# Grill_simple_bord_onedirect.net
KiCad netlist of a schematic drawn in EAGLE
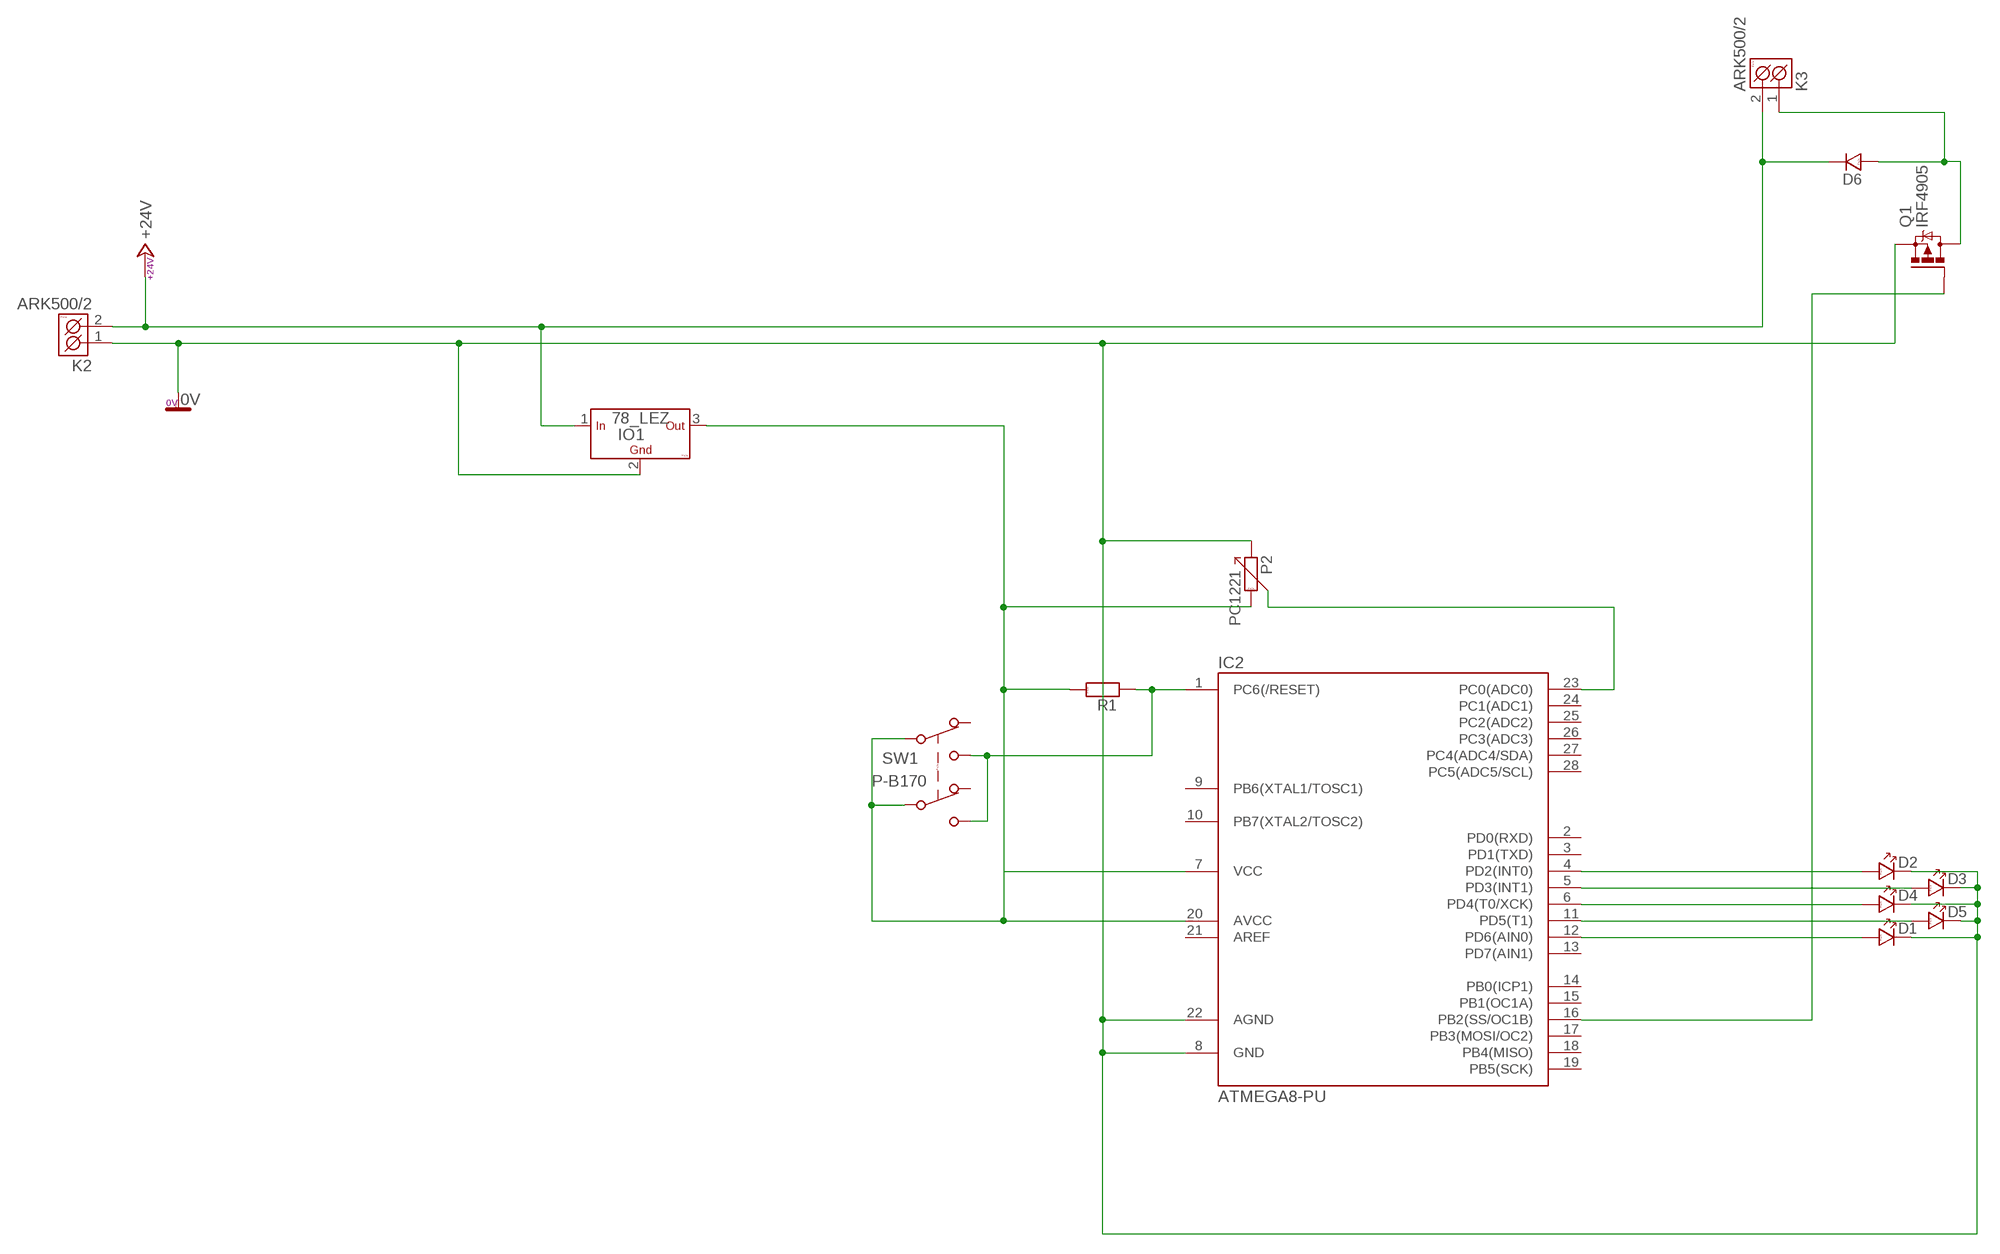
[diagram p0: schematic, sheet 1]

(export (version "E")
  (design (tool "Eeschema 10.0.6"))
  (components
    (comp (ref "D1")
      (value "LED_5")
      (footprint "eagle-import:LED_5")
      (libsource (lib "eagle-import") (part "LED_5"))
    )
    (comp (ref "D2")
      (value "LED_5")
      (footprint "eagle-import:LED_5")
      (libsource (lib "eagle-import") (part "LED_5"))
    )
    (comp (ref "D3")
      (value "LED_5")
      (footprint "eagle-import:LED_5")
      (libsource (lib "eagle-import") (part "LED_5"))
    )
    (comp (ref "D4")
      (value "LED_5")
      (footprint "eagle-import:LED_5")
      (libsource (lib "eagle-import") (part "LED_5"))
    )
    (comp (ref "D5")
      (value "LED_5")
      (footprint "eagle-import:LED_5")
      (libsource (lib "eagle-import") (part "LED_5"))
    )
    (comp (ref "D6")
      (value "D_10")
      (footprint "eagle-import:DO41")
      (libsource (lib "eagle-import") (part "D_10"))
    )
    (comp (ref "IC2")
      (value "ATMEGA8-PU")
      (footprint "eagle-import:DIL28-3")
      (libsource (lib "eagle-import") (part "ATMEGA8-PU"))
    )
    (comp (ref "IO1")
      (value "78_LEZ")
      (footprint "eagle-import:TO-220")
      (libsource (lib "eagle-import") (part "78?_LEZ"))
    )
    (comp (ref "K2")
      (value "ARK500/2")
      (footprint "eagle-import:ARK500_2")
      (libsource (lib "eagle-import") (part "ARK500/2"))
    )
    (comp (ref "K3")
      (value "ARK500/2")
      (footprint "eagle-import:ARK500_2")
      (libsource (lib "eagle-import") (part "ARK500/2"))
    )
    (comp (ref "P2")
      (value "PC1221")
      (footprint "eagle-import:PC1221")
      (libsource (lib "eagle-import") (part "PC1221"))
    )
    (comp (ref "Q1")
      (value "IRF4905")
      (footprint "eagle-import:TO220BH")
      (libsource (lib "eagle-import") (part "IRF4905"))
    )
    (comp (ref "R1")
      (value "R_7,5")
      (footprint "eagle-import:R-7,5")
      (libsource (lib "eagle-import") (part "R_7,5"))
    )
    (comp (ref "SW1")
      (value "P-B170")
      (footprint "eagle-import:P-B170")
      (libsource (lib "eagle-import") (part "P-B170"))
    )
  )
  (nets
    (net (code "1") (name "+24V") (class "Default")
      (node (ref "D6") (pin "K") (pinfunction "K_K") (pintype "passive"))
      (node (ref "IO1") (pin "1") (pinfunction "IN_1") (pintype "passive"))
      (node (ref "K2") (pin "2") (pinfunction "K2_2") (pintype "passive"))
      (node (ref "K3") (pin "2") (pinfunction "K2_2") (pintype "passive"))
    )
    (net (code "2") (name "0V") (class "Default")
      (node (ref "D1") (pin "K") (pinfunction "K_K") (pintype "passive"))
      (node (ref "D2") (pin "K") (pinfunction "K_K") (pintype "passive"))
      (node (ref "D3") (pin "K") (pinfunction "K_K") (pintype "passive"))
      (node (ref "D4") (pin "K") (pinfunction "K_K") (pintype "passive"))
      (node (ref "D5") (pin "K") (pinfunction "K_K") (pintype "passive"))
      (node (ref "IC2") (pin "22") (pinfunction "AGND_22") (pintype "power_in"))
      (node (ref "IC2") (pin "8") (pinfunction "GND_8") (pintype "power_in"))
      (node (ref "IO1") (pin "2") (pinfunction "GND_2") (pintype "passive"))
      (node (ref "K2") (pin "1") (pinfunction "K1_1") (pintype "passive"))
      (node (ref "P2") (pin "1") (pinfunction "1_1") (pintype "passive"))
      (node (ref "Q1") (pin "S") (pinfunction "S_S") (pintype "passive"))
    )
    (net (code "3") (name "Net-(IC2-AVCC)") (class "Default")
      (node (ref "IC2") (pin "20") (pinfunction "AVCC_20") (pintype "passive"))
      (node (ref "IC2") (pin "7") (pinfunction "VCC_7") (pintype "power_in"))
      (node (ref "IO1") (pin "3") (pinfunction "OUT_3") (pintype "passive"))
      (node (ref "P2") (pin "2") (pinfunction "2_2") (pintype "passive"))
      (node (ref "R1") (pin "2") (pinfunction "2_2") (pintype "passive"))
      (node (ref "SW1") (pin "3") (pinfunction "X1_3") (pintype "passive"))
      (node (ref "SW1") (pin "6") (pinfunction "X2_6") (pintype "passive"))
    )
    (net (code "4") (name "Net-(IC2-PB2(SS{slash}OC1B))") (class "Default")
      (node (ref "IC2") (pin "16") (pinfunction "PB2(SS/OC1B)_16") (pintype "bidirectional"))
      (node (ref "Q1") (pin "G") (pinfunction "G_G") (pintype "passive"))
    )
    (net (code "5") (name "Net-(IC2-PC0(ADC0))") (class "Default")
      (node (ref "IC2") (pin "23") (pinfunction "PC0(ADC0)_23") (pintype "bidirectional"))
      (node (ref "P2") (pin "3") (pinfunction "3_3") (pintype "passive"))
    )
    (net (code "6") (name "Net-(IC2-PC6({slash}RESET))") (class "Default")
      (node (ref "IC2") (pin "1") (pinfunction "PC6(/RESET)_1") (pintype "bidirectional"))
      (node (ref "R1") (pin "1") (pinfunction "1_1") (pintype "passive"))
      (node (ref "SW1") (pin "2") (pinfunction "R1_2") (pintype "passive"))
      (node (ref "SW1") (pin "5") (pinfunction "R2_5") (pintype "passive"))
    )
    (net (code "7") (name "Net-(IC2-PD2(INT0))") (class "Default")
      (node (ref "D2") (pin "A") (pinfunction "A_A") (pintype "passive"))
      (node (ref "IC2") (pin "4") (pinfunction "PD2(INT0)_4") (pintype "bidirectional"))
    )
    (net (code "8") (name "Net-(IC2-PD3(INT1))") (class "Default")
      (node (ref "D3") (pin "A") (pinfunction "A_A") (pintype "passive"))
      (node (ref "IC2") (pin "5") (pinfunction "PD3(INT1)_5") (pintype "bidirectional"))
    )
    (net (code "9") (name "Net-(IC2-PD4(T0{slash}XCK))") (class "Default")
      (node (ref "D4") (pin "A") (pinfunction "A_A") (pintype "passive"))
      (node (ref "IC2") (pin "6") (pinfunction "PD4(T0/XCK)_6") (pintype "bidirectional"))
    )
    (net (code "10") (name "Net-(IC2-PD5(T1))") (class "Default")
      (node (ref "D5") (pin "A") (pinfunction "A_A") (pintype "passive"))
      (node (ref "IC2") (pin "11") (pinfunction "PD5(T1)_11") (pintype "bidirectional"))
    )
    (net (code "11") (name "Net-(IC2-PD6(AIN0))") (class "Default")
      (node (ref "D1") (pin "A") (pinfunction "A_A") (pintype "passive"))
      (node (ref "IC2") (pin "12") (pinfunction "PD6(AIN0)_12") (pintype "bidirectional"))
    )
    (net (code "12") (name "Net-(K3-K1)") (class "Default")
      (node (ref "D6") (pin "A") (pinfunction "A_A") (pintype "passive"))
      (node (ref "K3") (pin "1") (pinfunction "K1_1") (pintype "passive"))
      (node (ref "Q1") (pin "D") (pinfunction "D_D") (pintype "passive"))
    )
    (net (code "13") (name "unconnected-(IC2-AREF-Pad21)") (class "Default")
      (node (ref "IC2") (pin "21") (pinfunction "AREF_21") (pintype "passive"))
    )
    (net (code "14") (name "unconnected-(IC2-PB0(ICP1)-Pad14)") (class "Default")
      (node (ref "IC2") (pin "14") (pinfunction "PB0(ICP1)_14") (pintype "bidirectional"))
    )
    (net (code "15") (name "unconnected-(IC2-PB1(OC1A)-Pad15)") (class "Default")
      (node (ref "IC2") (pin "15") (pinfunction "PB1(OC1A)_15") (pintype "bidirectional"))
    )
    (net (code "16") (name "unconnected-(IC2-PB3(MOSI{slash}OC2)-Pad17)") (class "Default")
      (node (ref "IC2") (pin "17") (pinfunction "PB3(MOSI/OC2)_17") (pintype "bidirectional"))
    )
    (net (code "17") (name "unconnected-(IC2-PB4(MISO)-Pad18)") (class "Default")
      (node (ref "IC2") (pin "18") (pinfunction "PB4(MISO)_18") (pintype "bidirectional"))
    )
    (net (code "18") (name "unconnected-(IC2-PB5(SCK)-Pad19)") (class "Default")
      (node (ref "IC2") (pin "19") (pinfunction "PB5(SCK)_19") (pintype "bidirectional"))
    )
    (net (code "19") (name "unconnected-(IC2-PB6(XTAL1{slash}TOSC1)-Pad9)") (class "Default")
      (node (ref "IC2") (pin "9") (pinfunction "PB6(XTAL1/TOSC1)_9") (pintype "bidirectional"))
    )
    (net (code "20") (name "unconnected-(IC2-PB7(XTAL2{slash}TOSC2)-Pad10)") (class "Default")
      (node (ref "IC2") (pin "10") (pinfunction "PB7(XTAL2/TOSC2)_10") (pintype "bidirectional"))
    )
    (net (code "21") (name "unconnected-(IC2-PC1(ADC1)-Pad24)") (class "Default")
      (node (ref "IC2") (pin "24") (pinfunction "PC1(ADC1)_24") (pintype "bidirectional"))
    )
    (net (code "22") (name "unconnected-(IC2-PC2(ADC2)-Pad25)") (class "Default")
      (node (ref "IC2") (pin "25") (pinfunction "PC2(ADC2)_25") (pintype "bidirectional"))
    )
    (net (code "23") (name "unconnected-(IC2-PC3(ADC3)-Pad26)") (class "Default")
      (node (ref "IC2") (pin "26") (pinfunction "PC3(ADC3)_26") (pintype "bidirectional"))
    )
    (net (code "24") (name "unconnected-(IC2-PC4(ADC4{slash}SDA)-Pad27)") (class "Default")
      (node (ref "IC2") (pin "27") (pinfunction "PC4(ADC4/SDA)_27") (pintype "bidirectional"))
    )
    (net (code "25") (name "unconnected-(IC2-PC5(ADC5{slash}SCL)-Pad28)") (class "Default")
      (node (ref "IC2") (pin "28") (pinfunction "PC5(ADC5/SCL)_28") (pintype "bidirectional"))
    )
    (net (code "26") (name "unconnected-(IC2-PD0(RXD)-Pad2)") (class "Default")
      (node (ref "IC2") (pin "2") (pinfunction "PD0(RXD)_2") (pintype "bidirectional"))
    )
    (net (code "27") (name "unconnected-(IC2-PD1(TXD)-Pad3)") (class "Default")
      (node (ref "IC2") (pin "3") (pinfunction "PD1(TXD)_3") (pintype "bidirectional"))
    )
    (net (code "28") (name "unconnected-(IC2-PD7(AIN1)-Pad13)") (class "Default")
      (node (ref "IC2") (pin "13") (pinfunction "PD7(AIN1)_13") (pintype "bidirectional"))
    )
    (net (code "29") (name "unconnected-(SW1-S1-Pad1)") (class "Default")
      (node (ref "SW1") (pin "1") (pinfunction "S1_1") (pintype "passive"))
    )
    (net (code "30") (name "unconnected-(SW1-S2-Pad4)") (class "Default")
      (node (ref "SW1") (pin "4") (pinfunction "S2_4") (pintype "passive"))
    )
  )
)
